# DIOT_8ch_isoSPI.net
KiCad netlist of a schematic drawn in Altium Designer
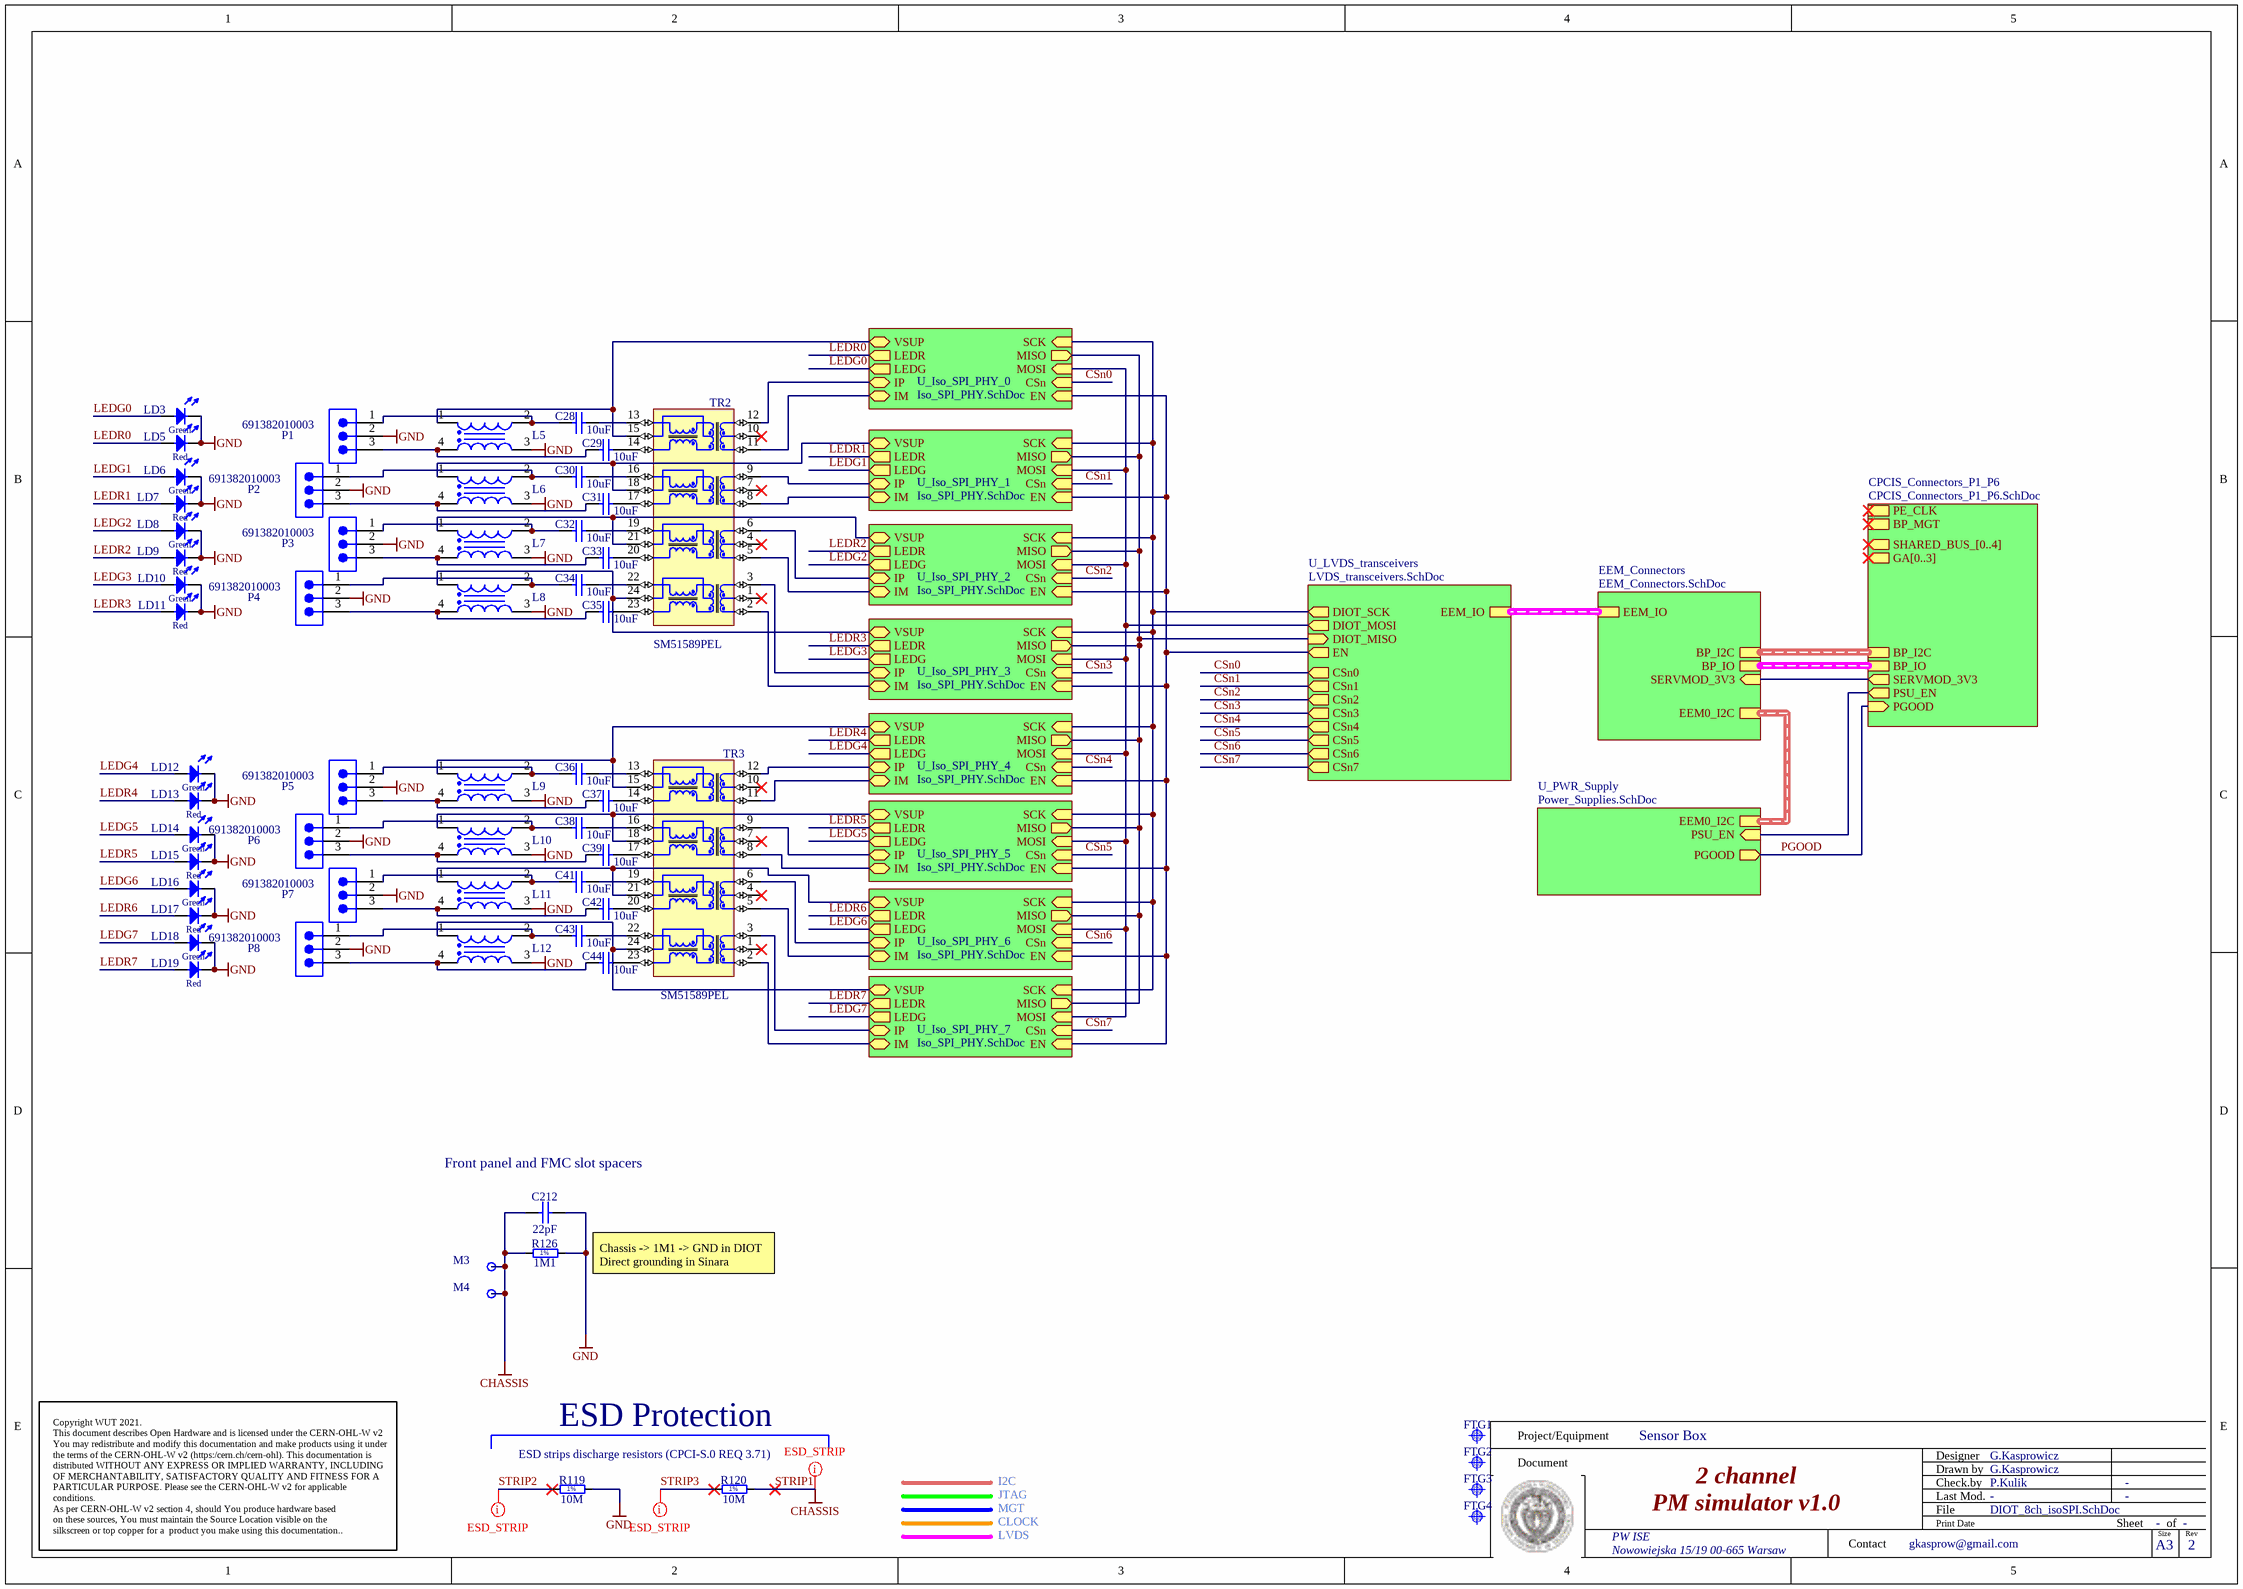
[diagram p0: DIOT_8ch_isoSPI.SchDoc]

(export (version "E")
  (design (tool "Eeschema 10.0.6"))
  (components
    (comp (ref "C28")
      (value "10uF")
      (footprint "CAPC1608X87N")
      (description "Non-polarised capacitor")
      (fields
        (field (name "PART NUMBER") "CC0603_10UF_6.3V_20%_X5R")
        (field (name "VOLTAGE") "6.3V")
        (field (name "AUTHOR") "CERN DEM JLC")
      )
      (libsource (lib "Capacitors") (part "Capacitor - non polarized"))
    )
    (comp (ref "C29")
      (value "10uF")
      (footprint "CAPC1608X87N")
      (description "Non-polarised capacitor")
      (fields
        (field (name "PART NUMBER") "CC0603_10UF_6.3V_20%_X5R")
        (field (name "VOLTAGE") "6.3V")
        (field (name "AUTHOR") "CERN DEM JLC")
      )
      (libsource (lib "Capacitors") (part "Capacitor - non polarized"))
    )
    (comp (ref "C30")
      (value "10uF")
      (footprint "CAPC1608X87N")
      (description "Non-polarised capacitor")
      (fields
        (field (name "PART NUMBER") "CC0603_10UF_6.3V_20%_X5R")
        (field (name "VOLTAGE") "6.3V")
        (field (name "AUTHOR") "CERN DEM JLC")
      )
      (libsource (lib "Capacitors") (part "Capacitor - non polarized"))
    )
    (comp (ref "C31")
      (value "10uF")
      (footprint "CAPC1608X87N")
      (description "Non-polarised capacitor")
      (fields
        (field (name "PART NUMBER") "CC0603_10UF_6.3V_20%_X5R")
        (field (name "VOLTAGE") "6.3V")
        (field (name "AUTHOR") "CERN DEM JLC")
      )
      (libsource (lib "Capacitors") (part "Capacitor - non polarized"))
    )
    (comp (ref "C32")
      (value "10uF")
      (footprint "CAPC1608X87N")
      (description "Non-polarised capacitor")
      (fields
        (field (name "PART NUMBER") "CC0603_10UF_6.3V_20%_X5R")
        (field (name "VOLTAGE") "6.3V")
        (field (name "AUTHOR") "CERN DEM JLC")
      )
      (libsource (lib "Capacitors") (part "Capacitor - non polarized"))
    )
    (comp (ref "C33")
      (value "10uF")
      (footprint "CAPC1608X87N")
      (description "Non-polarised capacitor")
      (fields
        (field (name "PART NUMBER") "CC0603_10UF_6.3V_20%_X5R")
        (field (name "VOLTAGE") "6.3V")
        (field (name "AUTHOR") "CERN DEM JLC")
      )
      (libsource (lib "Capacitors") (part "Capacitor - non polarized"))
    )
    (comp (ref "C34")
      (value "10uF")
      (footprint "CAPC1608X87N")
      (description "Non-polarised capacitor")
      (fields
        (field (name "PART NUMBER") "CC0603_10UF_6.3V_20%_X5R")
        (field (name "VOLTAGE") "6.3V")
        (field (name "AUTHOR") "CERN DEM JLC")
      )
      (libsource (lib "Capacitors") (part "Capacitor - non polarized"))
    )
    (comp (ref "C35")
      (value "10uF")
      (footprint "CAPC1608X87N")
      (description "Non-polarised capacitor")
      (fields
        (field (name "PART NUMBER") "CC0603_10UF_6.3V_20%_X5R")
        (field (name "VOLTAGE") "6.3V")
        (field (name "AUTHOR") "CERN DEM JLC")
      )
      (libsource (lib "Capacitors") (part "Capacitor - non polarized"))
    )
    (comp (ref "C36")
      (value "10uF")
      (footprint "CAPC1608X87N")
      (description "Non-polarised capacitor")
      (fields
        (field (name "PART NUMBER") "CC0603_10UF_6.3V_20%_X5R")
        (field (name "VOLTAGE") "6.3V")
        (field (name "AUTHOR") "CERN DEM JLC")
      )
      (libsource (lib "Capacitors") (part "Capacitor - non polarized"))
    )
    (comp (ref "C37")
      (value "10uF")
      (footprint "CAPC1608X87N")
      (description "Non-polarised capacitor")
      (fields
        (field (name "PART NUMBER") "CC0603_10UF_6.3V_20%_X5R")
        (field (name "VOLTAGE") "6.3V")
        (field (name "AUTHOR") "CERN DEM JLC")
      )
      (libsource (lib "Capacitors") (part "Capacitor - non polarized"))
    )
    (comp (ref "C38")
      (value "10uF")
      (footprint "CAPC1608X87N")
      (description "Non-polarised capacitor")
      (fields
        (field (name "PART NUMBER") "CC0603_10UF_6.3V_20%_X5R")
        (field (name "VOLTAGE") "6.3V")
        (field (name "AUTHOR") "CERN DEM JLC")
      )
      (libsource (lib "Capacitors") (part "Capacitor - non polarized"))
    )
    (comp (ref "C39")
      (value "10uF")
      (footprint "CAPC1608X87N")
      (description "Non-polarised capacitor")
      (fields
        (field (name "PART NUMBER") "CC0603_10UF_6.3V_20%_X5R")
        (field (name "VOLTAGE") "6.3V")
        (field (name "AUTHOR") "CERN DEM JLC")
      )
      (libsource (lib "Capacitors") (part "Capacitor - non polarized"))
    )
    (comp (ref "C41")
      (value "10uF")
      (footprint "CAPC1608X87N")
      (description "Non-polarised capacitor")
      (fields
        (field (name "PART NUMBER") "CC0603_10UF_6.3V_20%_X5R")
        (field (name "VOLTAGE") "6.3V")
        (field (name "AUTHOR") "CERN DEM JLC")
      )
      (libsource (lib "Capacitors") (part "Capacitor - non polarized"))
    )
    (comp (ref "C42")
      (value "10uF")
      (footprint "CAPC1608X87N")
      (description "Non-polarised capacitor")
      (fields
        (field (name "PART NUMBER") "CC0603_10UF_6.3V_20%_X5R")
        (field (name "VOLTAGE") "6.3V")
        (field (name "AUTHOR") "CERN DEM JLC")
      )
      (libsource (lib "Capacitors") (part "Capacitor - non polarized"))
    )
    (comp (ref "C43")
      (value "10uF")
      (footprint "CAPC1608X87N")
      (description "Non-polarised capacitor")
      (fields
        (field (name "PART NUMBER") "CC0603_10UF_6.3V_20%_X5R")
        (field (name "VOLTAGE") "6.3V")
        (field (name "AUTHOR") "CERN DEM JLC")
      )
      (libsource (lib "Capacitors") (part "Capacitor - non polarized"))
    )
    (comp (ref "C44")
      (value "10uF")
      (footprint "CAPC1608X87N")
      (description "Non-polarised capacitor")
      (fields
        (field (name "PART NUMBER") "CC0603_10UF_6.3V_20%_X5R")
        (field (name "VOLTAGE") "6.3V")
        (field (name "AUTHOR") "CERN DEM JLC")
      )
      (libsource (lib "Capacitors") (part "Capacitor - non polarized"))
    )
    (comp (ref "C212")
      (value "22pF")
      (footprint "CAPC1005X55N")
      (description "Non-polarised capacitor")
      (fields
        (field (name "PART NUMBER") "CC0402_22PF_50V_5%_C0G")
        (field (name "VOLTAGE") "50V")
        (field (name "AUTHOR") "CERN DEM JLC")
      )
      (libsource (lib "Capacitors") (part "Capacitor - non polarized"))
    )
    (comp (ref "FTG1")
      (value "Use only in PCB")
      (footprint "FIDUCIAL_TOP_C100-200")
      (description "Fiducial Target")
      (fields (field (name "PART NUMBER") "FIDUCIAL_TARGET_C100-200") (field (name "AUTHOR") "CERN DEM JLC"))
      (libsource (lib "Eletro-mechanical") (part "Fiducial Target"))
    )
    (comp (ref "FTG2")
      (value "Use only in PCB")
      (footprint "FIDUCIAL_TOP_S100-200")
      (description "Fiducial Target")
      (fields (field (name "PART NUMBER") "FIDUCIAL_TARGET_S100-200") (field (name "AUTHOR") "CERN DEM JLC"))
      (libsource (lib "Eletro-mechanical") (part "Fiducial Target"))
    )
    (comp (ref "FTG3")
      (value "Use only in PCB")
      (footprint "FIDUCIAL_TOP_S100-200")
      (description "Fiducial Target")
      (fields (field (name "PART NUMBER") "FIDUCIAL_TARGET_S100-200") (field (name "AUTHOR") "CERN DEM JLC"))
      (libsource (lib "Eletro-mechanical") (part "Fiducial Target"))
    )
    (comp (ref "FTG4")
      (value "Use only in PCB")
      (footprint "FIDUCIAL_TOP_S100-200")
      (description "Fiducial Target")
      (fields (field (name "PART NUMBER") "FIDUCIAL_TARGET_S100-200") (field (name "AUTHOR") "CERN DEM JLC"))
      (libsource (lib "Eletro-mechanical") (part "Fiducial Target"))
    )
    (comp (ref "L5")
      (value "100µH, 0.3A")
      (footprint "WE-DD_7332")
      (description "WE-DD SMT Shielded Coupled Inductor, size 7332, 100µH, 0.3A, 1730mΩ")
      (fields
        (field (name "MANUFACTURER PART NUMBER") "744878101")
        (field (name "MANUFACTURER") "Wurth Elektronik")
      )
      (libsource (lib "WE-DD (rev22b)") (part "744878101"))
    )
    (comp (ref "L6")
      (value "100µH, 0.3A")
      (footprint "WE-DD_7332")
      (description "WE-DD SMT Shielded Coupled Inductor, size 7332, 100µH, 0.3A, 1730mΩ")
      (fields
        (field (name "MANUFACTURER PART NUMBER") "744878101")
        (field (name "MANUFACTURER") "Wurth Elektronik")
      )
      (libsource (lib "WE-DD (rev22b)") (part "744878101"))
    )
    (comp (ref "L7")
      (value "100µH, 0.3A")
      (footprint "WE-DD_7332")
      (description "WE-DD SMT Shielded Coupled Inductor, size 7332, 100µH, 0.3A, 1730mΩ")
      (fields
        (field (name "MANUFACTURER PART NUMBER") "744878101")
        (field (name "MANUFACTURER") "Wurth Elektronik")
      )
      (libsource (lib "WE-DD (rev22b)") (part "744878101"))
    )
    (comp (ref "L8")
      (value "100µH, 0.3A")
      (footprint "WE-DD_7332")
      (description "WE-DD SMT Shielded Coupled Inductor, size 7332, 100µH, 0.3A, 1730mΩ")
      (fields
        (field (name "MANUFACTURER PART NUMBER") "744878101")
        (field (name "MANUFACTURER") "Wurth Elektronik")
      )
      (libsource (lib "WE-DD (rev22b)") (part "744878101"))
    )
    (comp (ref "L9")
      (value "100µH, 0.3A")
      (footprint "WE-DD_7332")
      (description "WE-DD SMT Shielded Coupled Inductor, size 7332, 100µH, 0.3A, 1730mΩ")
      (fields
        (field (name "MANUFACTURER PART NUMBER") "744878101")
        (field (name "MANUFACTURER") "Wurth Elektronik")
      )
      (libsource (lib "WE-DD (rev22b)") (part "744878101"))
    )
    (comp (ref "L10")
      (value "100µH, 0.3A")
      (footprint "WE-DD_7332")
      (description "WE-DD SMT Shielded Coupled Inductor, size 7332, 100µH, 0.3A, 1730mΩ")
      (fields
        (field (name "MANUFACTURER PART NUMBER") "744878101")
        (field (name "MANUFACTURER") "Wurth Elektronik")
      )
      (libsource (lib "WE-DD (rev22b)") (part "744878101"))
    )
    (comp (ref "L11")
      (value "100µH, 0.3A")
      (footprint "WE-DD_7332")
      (description "WE-DD SMT Shielded Coupled Inductor, size 7332, 100µH, 0.3A, 1730mΩ")
      (fields
        (field (name "MANUFACTURER PART NUMBER") "744878101")
        (field (name "MANUFACTURER") "Wurth Elektronik")
      )
      (libsource (lib "WE-DD (rev22b)") (part "744878101"))
    )
    (comp (ref "L12")
      (value "100µH, 0.3A")
      (footprint "WE-DD_7332")
      (description "WE-DD SMT Shielded Coupled Inductor, size 7332, 100µH, 0.3A, 1730mΩ")
      (fields
        (field (name "MANUFACTURER PART NUMBER") "744878101")
        (field (name "MANUFACTURER") "Wurth Elektronik")
      )
      (libsource (lib "WE-DD (rev22b)") (part "744878101"))
    )
    (comp (ref "LD3")
      (value "Green")
      (footprint "LED_AVAGO_HSME-C120")
      (description "LED Green 1C 2A")
      (fields
        (field (name "PART NUMBER") "LED_AVAGO_HSME-C120")
        (field (name "MANUFACTURER") "AVAGO TECHNOLOGIES")
        (field (name "AUTHOR") "CERN DEM JMW")
      )
      (libsource (lib "ICs And Semiconductors") (part "LED Green 1C 2A"))
    )
    (comp (ref "LD5")
      (value "Red")
      (footprint "LED_AVAGO_HSMC-C120")
      (description "LED Red 1C 2A")
      (fields
        (field (name "PART NUMBER") "LED_AVAGO_HSMC-C120")
        (field (name "MANUFACTURER") "AVAGO TECHNOLOGIES")
        (field (name "AUTHOR") "CERN DEM JMW")
      )
      (libsource (lib "ICs And Semiconductors") (part "LED Red 1C 2A"))
    )
    (comp (ref "LD6")
      (value "Green")
      (footprint "LED_AVAGO_HSME-C120")
      (description "LED Green 1C 2A")
      (fields
        (field (name "PART NUMBER") "LED_AVAGO_HSME-C120")
        (field (name "MANUFACTURER") "AVAGO TECHNOLOGIES")
        (field (name "AUTHOR") "CERN DEM JMW")
      )
      (libsource (lib "ICs And Semiconductors") (part "LED Green 1C 2A"))
    )
    (comp (ref "LD7")
      (value "Red")
      (footprint "LED_AVAGO_HSMC-C120")
      (description "LED Red 1C 2A")
      (fields
        (field (name "PART NUMBER") "LED_AVAGO_HSMC-C120")
        (field (name "MANUFACTURER") "AVAGO TECHNOLOGIES")
        (field (name "AUTHOR") "CERN DEM JMW")
      )
      (libsource (lib "ICs And Semiconductors") (part "LED Red 1C 2A"))
    )
    (comp (ref "LD8")
      (value "Green")
      (footprint "LED_AVAGO_HSME-C120")
      (description "LED Green 1C 2A")
      (fields
        (field (name "PART NUMBER") "LED_AVAGO_HSME-C120")
        (field (name "MANUFACTURER") "AVAGO TECHNOLOGIES")
        (field (name "AUTHOR") "CERN DEM JMW")
      )
      (libsource (lib "ICs And Semiconductors") (part "LED Green 1C 2A"))
    )
    (comp (ref "LD9")
      (value "Red")
      (footprint "LED_AVAGO_HSMC-C120")
      (description "LED Red 1C 2A")
      (fields
        (field (name "PART NUMBER") "LED_AVAGO_HSMC-C120")
        (field (name "MANUFACTURER") "AVAGO TECHNOLOGIES")
        (field (name "AUTHOR") "CERN DEM JMW")
      )
      (libsource (lib "ICs And Semiconductors") (part "LED Red 1C 2A"))
    )
    (comp (ref "LD10")
      (value "Green")
      (footprint "LED_AVAGO_HSME-C120")
      (description "LED Green 1C 2A")
      (fields
        (field (name "PART NUMBER") "LED_AVAGO_HSME-C120")
        (field (name "MANUFACTURER") "AVAGO TECHNOLOGIES")
        (field (name "AUTHOR") "CERN DEM JMW")
      )
      (libsource (lib "ICs And Semiconductors") (part "LED Green 1C 2A"))
    )
    (comp (ref "LD11")
      (value "Red")
      (footprint "LED_AVAGO_HSMC-C120")
      (description "LED Red 1C 2A")
      (fields
        (field (name "PART NUMBER") "LED_AVAGO_HSMC-C120")
        (field (name "MANUFACTURER") "AVAGO TECHNOLOGIES")
        (field (name "AUTHOR") "CERN DEM JMW")
      )
      (libsource (lib "ICs And Semiconductors") (part "LED Red 1C 2A"))
    )
    (comp (ref "LD12")
      (value "Green")
      (footprint "LED_AVAGO_HSME-C120")
      (description "LED Green 1C 2A")
      (fields
        (field (name "PART NUMBER") "LED_AVAGO_HSME-C120")
        (field (name "MANUFACTURER") "AVAGO TECHNOLOGIES")
        (field (name "AUTHOR") "CERN DEM JMW")
      )
      (libsource (lib "ICs And Semiconductors") (part "LED Green 1C 2A"))
    )
    (comp (ref "LD13")
      (value "Red")
      (footprint "LED_AVAGO_HSMC-C120")
      (description "LED Red 1C 2A")
      (fields
        (field (name "PART NUMBER") "LED_AVAGO_HSMC-C120")
        (field (name "MANUFACTURER") "AVAGO TECHNOLOGIES")
        (field (name "AUTHOR") "CERN DEM JMW")
      )
      (libsource (lib "ICs And Semiconductors") (part "LED Red 1C 2A"))
    )
    (comp (ref "LD14")
      (value "Green")
      (footprint "LED_AVAGO_HSME-C120")
      (description "LED Green 1C 2A")
      (fields
        (field (name "PART NUMBER") "LED_AVAGO_HSME-C120")
        (field (name "MANUFACTURER") "AVAGO TECHNOLOGIES")
        (field (name "AUTHOR") "CERN DEM JMW")
      )
      (libsource (lib "ICs And Semiconductors") (part "LED Green 1C 2A"))
    )
    (comp (ref "LD15")
      (value "Red")
      (footprint "LED_AVAGO_HSMC-C120")
      (description "LED Red 1C 2A")
      (fields
        (field (name "PART NUMBER") "LED_AVAGO_HSMC-C120")
        (field (name "MANUFACTURER") "AVAGO TECHNOLOGIES")
        (field (name "AUTHOR") "CERN DEM JMW")
      )
      (libsource (lib "ICs And Semiconductors") (part "LED Red 1C 2A"))
    )
    (comp (ref "LD16")
      (value "Green")
      (footprint "LED_AVAGO_HSME-C120")
      (description "LED Green 1C 2A")
      (fields
        (field (name "PART NUMBER") "LED_AVAGO_HSME-C120")
        (field (name "MANUFACTURER") "AVAGO TECHNOLOGIES")
        (field (name "AUTHOR") "CERN DEM JMW")
      )
      (libsource (lib "ICs And Semiconductors") (part "LED Green 1C 2A"))
    )
    (comp (ref "LD17")
      (value "Red")
      (footprint "LED_AVAGO_HSMC-C120")
      (description "LED Red 1C 2A")
      (fields
        (field (name "PART NUMBER") "LED_AVAGO_HSMC-C120")
        (field (name "MANUFACTURER") "AVAGO TECHNOLOGIES")
        (field (name "AUTHOR") "CERN DEM JMW")
      )
      (libsource (lib "ICs And Semiconductors") (part "LED Red 1C 2A"))
    )
    (comp (ref "LD18")
      (value "Green")
      (footprint "LED_AVAGO_HSME-C120")
      (description "LED Green 1C 2A")
      (fields
        (field (name "PART NUMBER") "LED_AVAGO_HSME-C120")
        (field (name "MANUFACTURER") "AVAGO TECHNOLOGIES")
        (field (name "AUTHOR") "CERN DEM JMW")
      )
      (libsource (lib "ICs And Semiconductors") (part "LED Green 1C 2A"))
    )
    (comp (ref "LD19")
      (value "Red")
      (footprint "LED_AVAGO_HSMC-C120")
      (description "LED Red 1C 2A")
      (fields
        (field (name "PART NUMBER") "LED_AVAGO_HSMC-C120")
        (field (name "MANUFACTURER") "AVAGO TECHNOLOGIES")
        (field (name "AUTHOR") "CERN DEM JMW")
      )
      (libsource (lib "ICs And Semiconductors") (part "LED Red 1C 2A"))
    )
    (comp (ref "M3")
      (value "Plated Hole")
      (footprint "MTG300_600")
      (description "Single Terminal Socket")
      (fields (field (name "PART NUMBER") "PLATED_HOLE3.0_PAD6.0") (field (name "AUTHOR") "CERN DEM JLC"))
      (libsource (lib "Eletro-mechanical") (part "Single Terminal Socket"))
    )
    (comp (ref "M4")
      (value "Plated Hole")
      (footprint "MTG300_600")
      (description "Single Terminal Socket")
      (fields (field (name "PART NUMBER") "PLATED_HOLE3.0_PAD6.0") (field (name "AUTHOR") "CERN DEM JLC"))
      (libsource (lib "Eletro-mechanical") (part "Single Terminal Socket"))
    )
    (comp (ref "P1")
      (value "691382010003")
      (footprint "691382010003")
      (description "WR-TBL Series 382 Horizontal PCB Header, THT, pitch 2.5mm, 03p")
      (fields (field (name "MANUFACTURER") "Wurth Elektronik"))
      (libsource (lib "Altium_WR-TBL_Pluggable Connector (rev25b)") (part "691382010003"))
    )
    (comp (ref "P2")
      (value "691382010003")
      (footprint "691382010003")
      (description "WR-TBL Series 382 Horizontal PCB Header, THT, pitch 2.5mm, 03p")
      (fields (field (name "MANUFACTURER") "Wurth Elektronik"))
      (libsource (lib "Altium_WR-TBL_Pluggable Connector (rev25b)") (part "691382010003"))
    )
    (comp (ref "P3")
      (value "691382010003")
      (footprint "691382010003")
      (description "WR-TBL Series 382 Horizontal PCB Header, THT, pitch 2.5mm, 03p")
      (fields (field (name "MANUFACTURER") "Wurth Elektronik"))
      (libsource (lib "Altium_WR-TBL_Pluggable Connector (rev25b)") (part "691382010003"))
    )
    (comp (ref "P4")
      (value "691382010003")
      (footprint "691382010003")
      (description "WR-TBL Series 382 Horizontal PCB Header, THT, pitch 2.5mm, 03p")
      (fields (field (name "MANUFACTURER") "Wurth Elektronik"))
      (libsource (lib "Altium_WR-TBL_Pluggable Connector (rev25b)") (part "691382010003"))
    )
    (comp (ref "P5")
      (value "691382010003")
      (footprint "691382010003")
      (description "WR-TBL Series 382 Horizontal PCB Header, THT, pitch 2.5mm, 03p")
      (fields (field (name "MANUFACTURER") "Wurth Elektronik"))
      (libsource (lib "Altium_WR-TBL_Pluggable Connector (rev25b)") (part "691382010003"))
    )
    (comp (ref "P6")
      (value "691382010003")
      (footprint "691382010003")
      (description "WR-TBL Series 382 Horizontal PCB Header, THT, pitch 2.5mm, 03p")
      (fields (field (name "MANUFACTURER") "Wurth Elektronik"))
      (libsource (lib "Altium_WR-TBL_Pluggable Connector (rev25b)") (part "691382010003"))
    )
    (comp (ref "P7")
      (value "691382010003")
      (footprint "691382010003")
      (description "WR-TBL Series 382 Horizontal PCB Header, THT, pitch 2.5mm, 03p")
      (fields (field (name "MANUFACTURER") "Wurth Elektronik"))
      (libsource (lib "Altium_WR-TBL_Pluggable Connector (rev25b)") (part "691382010003"))
    )
    (comp (ref "P8")
      (value "691382010003")
      (footprint "691382010003")
      (description "WR-TBL Series 382 Horizontal PCB Header, THT, pitch 2.5mm, 03p")
      (fields (field (name "MANUFACTURER") "Wurth Elektronik"))
      (libsource (lib "Altium_WR-TBL_Pluggable Connector (rev25b)") (part "691382010003"))
    )
    (comp (ref "R119")
      (value "10M")
      (footprint "RESC2113X55N")
      (description "Resistor - 1%")
      (fields
        (field (name "PART NUMBER") "R0805_10M_1%_0.125W_100PPM_VISHAY_CRCW e3")
        (field (name "POWER") "0.125W")
        (field (name "AUTHOR") "CERN DEM BC")
      )
      (libsource (lib "Resistors") (part "Resistor - 1%"))
    )
    (comp (ref "R120")
      (value "10M")
      (footprint "RESC2113X55N")
      (description "Resistor - 1%")
      (fields
        (field (name "PART NUMBER") "R0805_10M_1%_0.125W_100PPM_VISHAY_CRCW e3")
        (field (name "POWER") "0.125W")
        (field (name "AUTHOR") "CERN DEM BC")
      )
      (libsource (lib "Resistors") (part "Resistor - 1%"))
    )
    (comp (ref "R126")
      (value "1M1")
      (footprint "RESC2012X60N")
      (description "Resistor - 1%")
      (fields
        (field (name "PART NUMBER") "R0805_1M1_1%_0.125W_100PPM")
        (field (name "MANUFACTURER") "GENERIC")
        (field (name "AUTHOR") "CERN DEM JLC")
      )
      (libsource (lib "Resistors") (part "Resistor - 1%"))
    )
    (comp (ref "TR2")
      (value "~")
      (footprint "XFMR_BOURNS_SM51589P")
      (description "LAN 10/100/1000 Base-T Transformer (PoE) Modules")
      (fields
        (field (name "PART NUMBER") "XFMR_BOURNS_SM51589PEL")
        (field (name "MANUFACTURER") "BOURNS")
        (field (name "MANUFACTURER PART NUMBER") "SM51589PEL")
        (field (name "AUTHOR") "CERN DEM JLC")
      )
      (libsource (lib "Inductors & Transformers") (part "XFMR_BOURNS_SM51589PEL"))
    )
    (comp (ref "TR3")
      (value "~")
      (footprint "XFMR_BOURNS_SM51589P")
      (description "LAN 10/100/1000 Base-T Transformer (PoE) Modules")
      (fields
        (field (name "PART NUMBER") "XFMR_BOURNS_SM51589PEL")
        (field (name "MANUFACTURER") "BOURNS")
        (field (name "MANUFACTURER PART NUMBER") "SM51589PEL")
        (field (name "AUTHOR") "CERN DEM JLC")
      )
      (libsource (lib "Inductors & Transformers") (part "XFMR_BOURNS_SM51589PEL"))
    )
  )
  (nets
    (net (code "18") (name "/IM") (class "Default")
      (node (ref "TR2") (pin "8") (pinfunction "8_8") (pintype "bidirectional"))
    )
    (net (code "19") (name "/IM_1") (class "Default")
      (node (ref "TR3") (pin "2") (pinfunction "2_2") (pintype "bidirectional"))
    )
    (net (code "20") (name "/IM_2") (class "Default")
      (node (ref "TR3") (pin "5") (pinfunction "5_5") (pintype "bidirectional"))
    )
    (net (code "21") (name "/IM_3") (class "Default")
      (node (ref "TR3") (pin "11") (pinfunction "11_11") (pintype "bidirectional"))
    )
    (net (code "22") (name "/IM_4") (class "Default")
      (node (ref "TR3") (pin "8") (pinfunction "8_8") (pintype "bidirectional"))
    )
    (net (code "23") (name "/IM_5") (class "Default")
      (node (ref "TR2") (pin "2") (pinfunction "2_2") (pintype "bidirectional"))
    )
    (net (code "24") (name "/IM_6") (class "Default")
      (node (ref "TR2") (pin "5") (pinfunction "5_5") (pintype "bidirectional"))
    )
    (net (code "25") (name "/IM_7") (class "Default")
      (node (ref "TR2") (pin "11") (pinfunction "11_11") (pintype "bidirectional"))
    )
    (net (code "26") (name "/IP") (class "Default")
      (node (ref "TR2") (pin "9") (pinfunction "9_9") (pintype "bidirectional"))
    )
    (net (code "27") (name "/IP_1") (class "Default")
      (node (ref "TR3") (pin "3") (pinfunction "3_3") (pintype "bidirectional"))
    )
    (net (code "28") (name "/IP_2") (class "Default")
      (node (ref "TR3") (pin "6") (pinfunction "6_6") (pintype "bidirectional"))
    )
    (net (code "29") (name "/IP_3") (class "Default")
      (node (ref "TR3") (pin "12") (pinfunction "12_12") (pintype "bidirectional"))
    )
    (net (code "30") (name "/IP_4") (class "Default")
      (node (ref "TR3") (pin "9") (pinfunction "9_9") (pintype "bidirectional"))
    )
    (net (code "31") (name "/IP_5") (class "Default")
      (node (ref "TR2") (pin "3") (pinfunction "3_3") (pintype "bidirectional"))
    )
    (net (code "32") (name "/IP_6") (class "Default")
      (node (ref "TR2") (pin "6") (pinfunction "6_6") (pintype "bidirectional"))
    )
    (net (code "33") (name "/IP_7") (class "Default")
      (node (ref "TR2") (pin "12") (pinfunction "12_12") (pintype "bidirectional"))
    )
    (net (code "34") (name "/LEDG0") (class "Default")
      (node (ref "LD3") (pin "2") (pinfunction "A_2") (pintype "passive"))
    )
    (net (code "35") (name "/LEDG1") (class "Default")
      (node (ref "LD6") (pin "2") (pinfunction "A_2") (pintype "passive"))
    )
    (net (code "36") (name "/LEDG2") (class "Default")
      (node (ref "LD8") (pin "2") (pinfunction "A_2") (pintype "passive"))
    )
    (net (code "37") (name "/LEDG3") (class "Default")
      (node (ref "LD10") (pin "2") (pinfunction "A_2") (pintype "passive"))
    )
    (net (code "38") (name "/LEDG4") (class "Default")
      (node (ref "LD12") (pin "2") (pinfunction "A_2") (pintype "passive"))
    )
    (net (code "39") (name "/LEDG5") (class "Default")
      (node (ref "LD14") (pin "2") (pinfunction "A_2") (pintype "passive"))
    )
    (net (code "40") (name "/LEDG6") (class "Default")
      (node (ref "LD16") (pin "2") (pinfunction "A_2") (pintype "passive"))
    )
    (net (code "41") (name "/LEDG7") (class "Default")
      (node (ref "LD18") (pin "2") (pinfunction "A_2") (pintype "passive"))
    )
    (net (code "42") (name "/LEDR0") (class "Default")
      (node (ref "LD5") (pin "2") (pinfunction "A_2") (pintype "passive"))
    )
    (net (code "43") (name "/LEDR1") (class "Default")
      (node (ref "LD7") (pin "2") (pinfunction "A_2") (pintype "passive"))
    )
    (net (code "44") (name "/LEDR2") (class "Default")
      (node (ref "LD9") (pin "2") (pinfunction "A_2") (pintype "passive"))
    )
    (net (code "45") (name "/LEDR3") (class "Default")
      (node (ref "LD11") (pin "2") (pinfunction "A_2") (pintype "passive"))
    )
    (net (code "46") (name "/LEDR4") (class "Default")
      (node (ref "LD13") (pin "2") (pinfunction "A_2") (pintype "passive"))
    )
    (net (code "47") (name "/LEDR5") (class "Default")
      (node (ref "LD15") (pin "2") (pinfunction "A_2") (pintype "passive"))
    )
    (net (code "48") (name "/LEDR6") (class "Default")
      (node (ref "LD17") (pin "2") (pinfunction "A_2") (pintype "passive"))
    )
    (net (code "49") (name "/LEDR7") (class "Default")
      (node (ref "LD19") (pin "2") (pinfunction "A_2") (pintype "passive"))
    )
    (net (code "57") (name "/STRIP2") (class "Default")
      (node (ref "R119") (pin "1") (pinfunction "1_1") (pintype "passive+no_connect"))
    )
    (net (code "58") (name "/STRIP3") (class "Default")
      (node (ref "R120") (pin "1") (pinfunction "1_1") (pintype "passive+no_connect"))
    )
    (net (code "59") (name "/VSUP") (class "Default")
      (node (ref "L6") (pin "1") (pinfunction "1_1") (pintype "passive"))
      (node (ref "TR2") (pin "18") (pinfunction "18_18") (pintype "bidirectional"))
    )
    (net (code "60") (name "/VSUP_1") (class "Default")
      (node (ref "L8") (pin "1") (pinfunction "1_1") (pintype "passive"))
      (node (ref "TR2") (pin "24") (pinfunction "24_24") (pintype "bidirectional"))
    )
    (net (code "61") (name "/VSUP_2") (class "Default")
      (node (ref "L5") (pin "1") (pinfunction "1_1") (pintype "passive"))
      (node (ref "TR2") (pin "15") (pinfunction "15_15") (pintype "bidirectional"))
    )
    (net (code "62") (name "/VSUP_3") (class "Default")
      (node (ref "L7") (pin "1") (pinfunction "1_1") (pintype "passive"))
      (node (ref "TR2") (pin "21") (pinfunction "21_21") (pintype "bidirectional"))
    )
    (net (code "63") (name "/VSUP_4") (class "Default")
      (node (ref "L11") (pin "1") (pinfunction "1_1") (pintype "passive"))
      (node (ref "TR3") (pin "21") (pinfunction "21_21") (pintype "bidirectional"))
    )
    (net (code "64") (name "/VSUP_5") (class "Default")
      (node (ref "L12") (pin "1") (pinfunction "1_1") (pintype "passive"))
      (node (ref "TR3") (pin "24") (pinfunction "24_24") (pintype "bidirectional"))
    )
    (net (code "65") (name "/VSUP_6") (class "Default")
      (node (ref "L9") (pin "1") (pinfunction "1_1") (pintype "passive"))
      (node (ref "TR3") (pin "15") (pinfunction "15_15") (pintype "bidirectional"))
    )
    (net (code "66") (name "/VSUP_7") (class "Default")
      (node (ref "L10") (pin "1") (pinfunction "1_1") (pintype "passive"))
      (node (ref "TR3") (pin "18") (pinfunction "18_18") (pintype "bidirectional"))
    )
    (net (code "67") (name "CHASSIS") (class "Default")
      (node (ref "C212") (pin "1") (pinfunction "1_1") (pintype "passive"))
      (node (ref "M3") (pin "1") (pinfunction "1_1") (pintype "bidirectional"))
      (node (ref "M4") (pin "1") (pinfunction "1_1") (pintype "bidirectional"))
      (node (ref "R120") (pin "2") (pinfunction "2_2") (pintype "passive"))
      (node (ref "R126") (pin "1") (pinfunction "1_1") (pintype "passive"))
    )
    (net (code "68") (name "GND") (class "Default")
      (node (ref "C212") (pin "2") (pinfunction "2_2") (pintype "passive"))
      (node (ref "L10") (pin "3") (pinfunction "3_3") (pintype "passive"))
      (node (ref "L11") (pin "3") (pinfunction "3_3") (pintype "passive"))
      (node (ref "L12") (pin "3") (pinfunction "3_3") (pintype "passive"))
      (node (ref "L5") (pin "3") (pinfunction "3_3") (pintype "passive"))
      (node (ref "L6") (pin "3") (pinfunction "3_3") (pintype "passive"))
      (node (ref "L7") (pin "3") (pinfunction "3_3") (pintype "passive"))
      (node (ref "L8") (pin "3") (pinfunction "3_3") (pintype "passive"))
      (node (ref "L9") (pin "3") (pinfunction "3_3") (pintype "passive"))
      (node (ref "LD10") (pin "1") (pinfunction "C_1") (pintype "passive"))
      (node (ref "LD11") (pin "1") (pinfunction "C_1") (pintype "passive"))
      (node (ref "LD12") (pin "1") (pinfunction "C_1") (pintype "passive"))
      (node (ref "LD13") (pin "1") (pinfunction "C_1") (pintype "passive"))
      (node (ref "LD14") (pin "1") (pinfunction "C_1") (pintype "passive"))
      (node (ref "LD15") (pin "1") (pinfunction "C_1") (pintype "passive"))
      (node (ref "LD16") (pin "1") (pinfunction "C_1") (pintype "passive"))
      (node (ref "LD17") (pin "1") (pinfunction "C_1") (pintype "passive"))
      (node (ref "LD18") (pin "1") (pinfunction "C_1") (pintype "passive"))
      (node (ref "LD19") (pin "1") (pinfunction "C_1") (pintype "passive"))
      (node (ref "LD3") (pin "1") (pinfunction "C_1") (pintype "passive"))
      (node (ref "LD5") (pin "1") (pinfunction "C_1") (pintype "passive"))
      (node (ref "LD6") (pin "1") (pinfunction "C_1") (pintype "passive"))
      (node (ref "LD7") (pin "1") (pinfunction "C_1") (pintype "passive"))
      (node (ref "LD8") (pin "1") (pinfunction "C_1") (pintype "passive"))
      (node (ref "LD9") (pin "1") (pinfunction "C_1") (pintype "passive"))
      (node (ref "P1") (pin "2") (pinfunction "2_2") (pintype "passive"))
      (node (ref "P2") (pin "2") (pinfunction "2_2") (pintype "passive"))
      (node (ref "P3") (pin "2") (pinfunction "2_2") (pintype "passive"))
      (node (ref "P4") (pin "2") (pinfunction "2_2") (pintype "passive"))
      (node (ref "P5") (pin "2") (pinfunction "2_2") (pintype "passive"))
      (node (ref "P6") (pin "2") (pinfunction "2_2") (pintype "passive"))
      (node (ref "P7") (pin "2") (pinfunction "2_2") (pintype "passive"))
      (node (ref "P8") (pin "2") (pinfunction "2_2") (pintype "passive"))
      (node (ref "R119") (pin "2") (pinfunction "2_2") (pintype "passive"))
      (node (ref "R126") (pin "2") (pinfunction "2_2") (pintype "passive"))
    )
    (net (code "69") (name "Net-(C28-Pad1)") (class "Default")
      (node (ref "C28") (pin "1") (pinfunction "1_1") (pintype "passive"))
      (node (ref "L5") (pin "2") (pinfunction "2_2") (pintype "passive"))
      (node (ref "P1") (pin "1") (pinfunction "1_1") (pintype "passive"))
    )
    (net (code "70") (name "Net-(C28-Pad2)") (class "Default")
      (node (ref "C28") (pin "2") (pinfunction "2_2") (pintype "passive"))
      (node (ref "TR2") (pin "13") (pinfunction "13_13") (pintype "bidirectional"))
    )
    (net (code "71") (name "Net-(C29-Pad1)") (class "Default")
      (node (ref "C29") (pin "1") (pinfunction "1_1") (pintype "passive"))
      (node (ref "L5") (pin "4") (pinfunction "4_4") (pintype "passive"))
      (node (ref "P1") (pin "3") (pinfunction "3_3") (pintype "passive"))
    )
    (net (code "72") (name "Net-(C29-Pad2)") (class "Default")
      (node (ref "C29") (pin "2") (pinfunction "2_2") (pintype "passive"))
      (node (ref "TR2") (pin "14") (pinfunction "14_14") (pintype "bidirectional"))
    )
    (net (code "73") (name "Net-(C30-Pad1)") (class "Default")
      (node (ref "C30") (pin "1") (pinfunction "1_1") (pintype "passive"))
      (node (ref "L6") (pin "2") (pinfunction "2_2") (pintype "passive"))
      (node (ref "P2") (pin "1") (pinfunction "1_1") (pintype "passive"))
    )
    (net (code "74") (name "Net-(C30-Pad2)") (class "Default")
      (node (ref "C30") (pin "2") (pinfunction "2_2") (pintype "passive"))
      (node (ref "TR2") (pin "16") (pinfunction "16_16") (pintype "bidirectional"))
    )
    (net (code "75") (name "Net-(C31-Pad1)") (class "Default")
      (node (ref "C31") (pin "1") (pinfunction "1_1") (pintype "passive"))
      (node (ref "L6") (pin "4") (pinfunction "4_4") (pintype "passive"))
      (node (ref "P2") (pin "3") (pinfunction "3_3") (pintype "passive"))
    )
    (net (code "76") (name "Net-(C31-Pad2)") (class "Default")
      (node (ref "C31") (pin "2") (pinfunction "2_2") (pintype "passive"))
      (node (ref "TR2") (pin "17") (pinfunction "17_17") (pintype "bidirectional"))
    )
    (net (code "77") (name "Net-(C32-Pad1)") (class "Default")
      (node (ref "C32") (pin "1") (pinfunction "1_1") (pintype "passive"))
      (node (ref "L7") (pin "2") (pinfunction "2_2") (pintype "passive"))
      (node (ref "P3") (pin "1") (pinfunction "1_1") (pintype "passive"))
    )
    (net (code "78") (name "Net-(C32-Pad2)") (class "Default")
      (node (ref "C32") (pin "2") (pinfunction "2_2") (pintype "passive"))
      (node (ref "TR2") (pin "19") (pinfunction "19_19") (pintype "bidirectional"))
    )
    (net (code "79") (name "Net-(C33-Pad1)") (class "Default")
      (node (ref "C33") (pin "1") (pinfunction "1_1") (pintype "passive"))
      (node (ref "L7") (pin "4") (pinfunction "4_4") (pintype "passive"))
      (node (ref "P3") (pin "3") (pinfunction "3_3") (pintype "passive"))
    )
    (net (code "80") (name "Net-(C33-Pad2)") (class "Default")
      (node (ref "C33") (pin "2") (pinfunction "2_2") (pintype "passive"))
      (node (ref "TR2") (pin "20") (pinfunction "20_20") (pintype "bidirectional"))
    )
    (net (code "81") (name "Net-(C34-Pad1)") (class "Default")
      (node (ref "C34") (pin "1") (pinfunction "1_1") (pintype "passive"))
      (node (ref "L8") (pin "2") (pinfunction "2_2") (pintype "passive"))
      (node (ref "P4") (pin "1") (pinfunction "1_1") (pintype "passive"))
    )
    (net (code "82") (name "Net-(C34-Pad2)") (class "Default")
      (node (ref "C34") (pin "2") (pinfunction "2_2") (pintype "passive"))
      (node (ref "TR2") (pin "22") (pinfunction "22_22") (pintype "bidirectional"))
    )
    (net (code "83") (name "Net-(C35-Pad1)") (class "Default")
      (node (ref "C35") (pin "1") (pinfunction "1_1") (pintype "passive"))
      (node (ref "L8") (pin "4") (pinfunction "4_4") (pintype "passive"))
      (node (ref "P4") (pin "3") (pinfunction "3_3") (pintype "passive"))
    )
    (net (code "84") (name "Net-(C35-Pad2)") (class "Default")
      (node (ref "C35") (pin "2") (pinfunction "2_2") (pintype "passive"))
      (node (ref "TR2") (pin "23") (pinfunction "23_23") (pintype "bidirectional"))
    )
    (net (code "85") (name "Net-(C36-Pad1)") (class "Default")
      (node (ref "C36") (pin "1") (pinfunction "1_1") (pintype "passive"))
      (node (ref "L9") (pin "2") (pinfunction "2_2") (pintype "passive"))
      (node (ref "P5") (pin "1") (pinfunction "1_1") (pintype "passive"))
    )
    (net (code "86") (name "Net-(C36-Pad2)") (class "Default")
      (node (ref "C36") (pin "2") (pinfunction "2_2") (pintype "passive"))
      (node (ref "TR3") (pin "13") (pinfunction "13_13") (pintype "bidirectional"))
    )
    (net (code "87") (name "Net-(C37-Pad1)") (class "Default")
      (node (ref "C37") (pin "1") (pinfunction "1_1") (pintype "passive"))
      (node (ref "L9") (pin "4") (pinfunction "4_4") (pintype "passive"))
      (node (ref "P5") (pin "3") (pinfunction "3_3") (pintype "passive"))
    )
    (net (code "88") (name "Net-(C37-Pad2)") (class "Default")
      (node (ref "C37") (pin "2") (pinfunction "2_2") (pintype "passive"))
      (node (ref "TR3") (pin "14") (pinfunction "14_14") (pintype "bidirectional"))
    )
    (net (code "89") (name "Net-(C38-Pad1)") (class "Default")
      (node (ref "C38") (pin "1") (pinfunction "1_1") (pintype "passive"))
      (node (ref "L10") (pin "2") (pinfunction "2_2") (pintype "passive"))
      (node (ref "P6") (pin "1") (pinfunction "1_1") (pintype "passive"))
    )
    (net (code "90") (name "Net-(C38-Pad2)") (class "Default")
      (node (ref "C38") (pin "2") (pinfunction "2_2") (pintype "passive"))
      (node (ref "TR3") (pin "16") (pinfunction "16_16") (pintype "bidirectional"))
    )
    (net (code "91") (name "Net-(C39-Pad1)") (class "Default")
      (node (ref "C39") (pin "1") (pinfunction "1_1") (pintype "passive"))
      (node (ref "L10") (pin "4") (pinfunction "4_4") (pintype "passive"))
      (node (ref "P6") (pin "3") (pinfunction "3_3") (pintype "passive"))
    )
    (net (code "92") (name "Net-(C39-Pad2)") (class "Default")
      (node (ref "C39") (pin "2") (pinfunction "2_2") (pintype "passive"))
      (node (ref "TR3") (pin "17") (pinfunction "17_17") (pintype "bidirectional"))
    )
    (net (code "93") (name "Net-(C41-Pad1)") (class "Default")
      (node (ref "C41") (pin "1") (pinfunction "1_1") (pintype "passive"))
      (node (ref "L11") (pin "2") (pinfunction "2_2") (pintype "passive"))
      (node (ref "P7") (pin "1") (pinfunction "1_1") (pintype "passive"))
    )
    (net (code "94") (name "Net-(C41-Pad2)") (class "Default")
      (node (ref "C41") (pin "2") (pinfunction "2_2") (pintype "passive"))
      (node (ref "TR3") (pin "19") (pinfunction "19_19") (pintype "bidirectional"))
    )
    (net (code "95") (name "Net-(C42-Pad1)") (class "Default")
      (node (ref "C42") (pin "1") (pinfunction "1_1") (pintype "passive"))
      (node (ref "L11") (pin "4") (pinfunction "4_4") (pintype "passive"))
      (node (ref "P7") (pin "3") (pinfunction "3_3") (pintype "passive"))
    )
    (net (code "96") (name "Net-(C42-Pad2)") (class "Default")
      (node (ref "C42") (pin "2") (pinfunction "2_2") (pintype "passive"))
      (node (ref "TR3") (pin "20") (pinfunction "20_20") (pintype "bidirectional"))
    )
    (net (code "97") (name "Net-(C43-Pad1)") (class "Default")
      (node (ref "C43") (pin "1") (pinfunction "1_1") (pintype "passive"))
      (node (ref "L12") (pin "2") (pinfunction "2_2") (pintype "passive"))
      (node (ref "P8") (pin "1") (pinfunction "1_1") (pintype "passive"))
    )
    (net (code "98") (name "Net-(C43-Pad2)") (class "Default")
      (node (ref "C43") (pin "2") (pinfunction "2_2") (pintype "passive"))
      (node (ref "TR3") (pin "22") (pinfunction "22_22") (pintype "bidirectional"))
    )
    (net (code "99") (name "Net-(C44-Pad1)") (class "Default")
      (node (ref "C44") (pin "1") (pinfunction "1_1") (pintype "passive"))
      (node (ref "L12") (pin "4") (pinfunction "4_4") (pintype "passive"))
      (node (ref "P8") (pin "3") (pinfunction "3_3") (pintype "passive"))
    )
    (net (code "100") (name "Net-(C44-Pad2)") (class "Default")
      (node (ref "C44") (pin "2") (pinfunction "2_2") (pintype "passive"))
      (node (ref "TR3") (pin "23") (pinfunction "23_23") (pintype "bidirectional"))
    )
    (net (code "101") (name "unconnected-(TR2-Pad1)") (class "Default")
      (node (ref "TR2") (pin "1") (pinfunction "1_1") (pintype "bidirectional+no_connect"))
    )
    (net (code "102") (name "unconnected-(TR2-Pad4)") (class "Default")
      (node (ref "TR2") (pin "4") (pinfunction "4_4") (pintype "bidirectional+no_connect"))
    )
    (net (code "103") (name "unconnected-(TR2-Pad7)") (class "Default")
      (node (ref "TR2") (pin "7") (pinfunction "7_7") (pintype "bidirectional+no_connect"))
    )
    (net (code "104") (name "unconnected-(TR2-Pad10)") (class "Default")
      (node (ref "TR2") (pin "10") (pinfunction "10_10") (pintype "bidirectional+no_connect"))
    )
    (net (code "105") (name "unconnected-(TR3-Pad1)") (class "Default")
      (node (ref "TR3") (pin "1") (pinfunction "1_1") (pintype "bidirectional+no_connect"))
    )
    (net (code "106") (name "unconnected-(TR3-Pad4)") (class "Default")
      (node (ref "TR3") (pin "4") (pinfunction "4_4") (pintype "bidirectional+no_connect"))
    )
    (net (code "107") (name "unconnected-(TR3-Pad7)") (class "Default")
      (node (ref "TR3") (pin "7") (pinfunction "7_7") (pintype "bidirectional+no_connect"))
    )
    (net (code "108") (name "unconnected-(TR3-Pad10)") (class "Default")
      (node (ref "TR3") (pin "10") (pinfunction "10_10") (pintype "bidirectional+no_connect"))
    )
  )
)
